# LeftBar2_SchDoc.net
KiCad netlist of a schematic drawn in Altium Designer
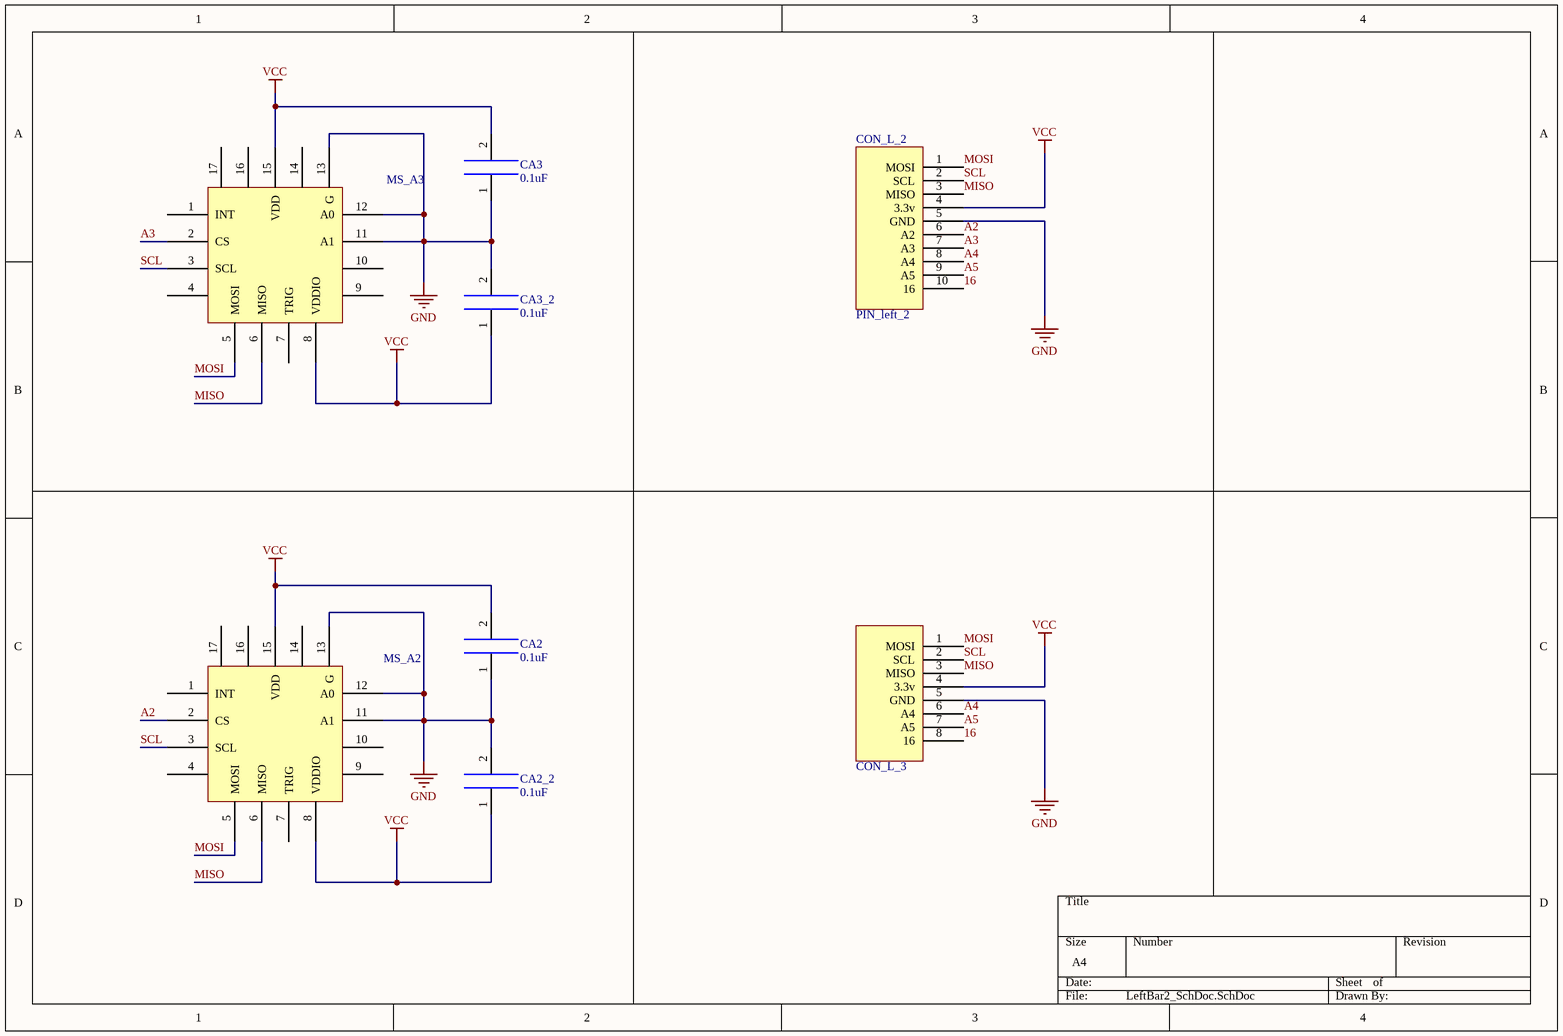
[diagram p0: LeftBar2_SchDoc.SchDoc]

(export (version "E")
  (design (tool "Eeschema 10.0.6"))
  (components
    (comp (ref "CA2")
      (value "0.1uF")
      (footprint "CAP_0603")
      (description "Capacitance")
      (libsource (lib "MagWaySchlib") (part "CAP"))
    )
    (comp (ref "CA2_2")
      (value "0.1uF")
      (footprint "CAP_0603")
      (description "Capacitance")
      (libsource (lib "MagWaySchlib") (part "CAP"))
    )
    (comp (ref "CA3")
      (value "0.1uF")
      (footprint "CAP_0603")
      (description "Capacitance")
      (libsource (lib "MagWaySchlib") (part "CAP"))
    )
    (comp (ref "CA3_2")
      (value "0.1uF")
      (footprint "CAP_0603")
      (description "Capacitance")
      (libsource (lib "MagWaySchlib") (part "CAP"))
    )
    (comp (ref "CON_L_2")
      (value "PIN_left_2")
      (footprint "PIN_Left_2")
      (libsource (lib "MagWaySchlib") (part "PIN_left_2"))
    )
    (comp (ref "CON_L_3")
      (value "PIN_left")
      (footprint "PIN_Left_3")
      (libsource (lib "MagWaySchlib") (part "PIN_left_3"))
    )
    (comp (ref "MS_A2")
      (value "MLX90393SLW ABA 011 RE")
      (footprint "MLX90393")
      (description "MLX90393 Sensor")
      (libsource (lib "MagWaySchlib") (part "MLX90393SLW ABA 011 RE"))
    )
    (comp (ref "MS_A3")
      (value "MLX90393SLW ABA 011 RE")
      (footprint "MLX90393")
      (description "MLX90393 Sensor")
      (libsource (lib "MagWaySchlib") (part "MLX90393SLW ABA 011 RE"))
    )
  )
  (nets
    (net (code "1") (name "/16") (class "Default")
      (node (ref "CON_L_2") (pin "10") (pinfunction "16_10") (pintype "passive"))
      (node (ref "CON_L_3") (pin "8") (pinfunction "16_8") (pintype "passive"))
    )
    (net (code "2") (name "/A2") (class "Default")
      (node (ref "CON_L_2") (pin "6") (pinfunction "A2_6") (pintype "passive"))
      (node (ref "MS_A2") (pin "2") (pinfunction "CS_2") (pintype "passive"))
    )
    (net (code "3") (name "/A3") (class "Default")
      (node (ref "CON_L_2") (pin "7") (pinfunction "A3_7") (pintype "passive"))
      (node (ref "MS_A3") (pin "2") (pinfunction "CS_2") (pintype "passive"))
    )
    (net (code "4") (name "/A4") (class "Default")
      (node (ref "CON_L_2") (pin "8") (pinfunction "A4_8") (pintype "passive"))
      (node (ref "CON_L_3") (pin "6") (pinfunction "A4_6") (pintype "passive"))
    )
    (net (code "5") (name "/A5") (class "Default")
      (node (ref "CON_L_2") (pin "9") (pinfunction "A5_9") (pintype "passive"))
      (node (ref "CON_L_3") (pin "7") (pinfunction "A5_7") (pintype "passive"))
    )
    (net (code "6") (name "/MISO") (class "Default")
      (node (ref "CON_L_2") (pin "3") (pinfunction "MISO_3") (pintype "passive"))
      (node (ref "CON_L_3") (pin "3") (pinfunction "MISO_3") (pintype "passive"))
      (node (ref "MS_A2") (pin "6") (pinfunction "MISO_6") (pintype "passive"))
      (node (ref "MS_A3") (pin "6") (pinfunction "MISO_6") (pintype "passive"))
    )
    (net (code "7") (name "/MOSI") (class "Default")
      (node (ref "CON_L_2") (pin "1") (pinfunction "MOSI_1") (pintype "passive"))
      (node (ref "CON_L_3") (pin "1") (pinfunction "MOSI_1") (pintype "passive"))
      (node (ref "MS_A2") (pin "5") (pinfunction "MOSI_5") (pintype "passive"))
      (node (ref "MS_A3") (pin "5") (pinfunction "MOSI_5") (pintype "passive"))
    )
    (net (code "8") (name "/SCL") (class "Default")
      (node (ref "CON_L_2") (pin "2") (pinfunction "SCL_2") (pintype "passive"))
      (node (ref "CON_L_3") (pin "2") (pinfunction "SCL_2") (pintype "passive"))
      (node (ref "MS_A2") (pin "3") (pinfunction "SCL_3") (pintype "passive"))
      (node (ref "MS_A3") (pin "3") (pinfunction "SCL_3") (pintype "passive"))
    )
    (net (code "9") (name "GND") (class "Default")
      (node (ref "CA2") (pin "1") (pintype "passive"))
      (node (ref "CA2_2") (pin "2") (pintype "passive"))
      (node (ref "CA3") (pin "1") (pintype "passive"))
      (node (ref "CA3_2") (pin "2") (pintype "passive"))
      (node (ref "CON_L_2") (pin "5") (pinfunction "GND_5") (pintype "passive"))
      (node (ref "CON_L_3") (pin "5") (pinfunction "GND_5") (pintype "passive"))
      (node (ref "MS_A2") (pin "11") (pinfunction "A1_11") (pintype "passive"))
      (node (ref "MS_A2") (pin "12") (pinfunction "A0_12") (pintype "passive"))
      (node (ref "MS_A2") (pin "13") (pinfunction "G_13") (pintype "passive"))
      (node (ref "MS_A3") (pin "11") (pinfunction "A1_11") (pintype "passive"))
      (node (ref "MS_A3") (pin "12") (pinfunction "A0_12") (pintype "passive"))
      (node (ref "MS_A3") (pin "13") (pinfunction "G_13") (pintype "passive"))
    )
    (net (code "10") (name "VCC") (class "Default")
      (node (ref "CA2") (pin "2") (pintype "passive"))
      (node (ref "CA2_2") (pin "1") (pintype "passive"))
      (node (ref "CA3") (pin "2") (pintype "passive"))
      (node (ref "CA3_2") (pin "1") (pintype "passive"))
      (node (ref "CON_L_2") (pin "4") (pinfunction "3.3v_4") (pintype "passive"))
      (node (ref "CON_L_3") (pin "4") (pinfunction "3.3v_4") (pintype "passive"))
      (node (ref "MS_A2") (pin "15") (pinfunction "VDD_15") (pintype "passive"))
      (node (ref "MS_A2") (pin "8") (pinfunction "VDDIO_8") (pintype "passive"))
      (node (ref "MS_A3") (pin "15") (pinfunction "VDD_15") (pintype "passive"))
      (node (ref "MS_A3") (pin "8") (pinfunction "VDDIO_8") (pintype "passive"))
    )
    (net (code "11") (name "unconnected-(MS_A2-INT-Pad1)") (class "Default")
      (node (ref "MS_A2") (pin "1") (pinfunction "INT_1") (pintype "passive"))
    )
    (net (code "12") (name "unconnected-(MS_A2-Pad4)") (class "Default")
      (node (ref "MS_A2") (pin "4") (pintype "passive"))
    )
    (net (code "13") (name "unconnected-(MS_A2-Pad9)") (class "Default")
      (node (ref "MS_A2") (pin "9") (pintype "passive"))
    )
    (net (code "14") (name "unconnected-(MS_A2-Pad10)") (class "Default")
      (node (ref "MS_A2") (pin "10") (pintype "passive"))
    )
    (net (code "15") (name "unconnected-(MS_A2-Pad14)") (class "Default")
      (node (ref "MS_A2") (pin "14") (pintype "passive"))
    )
    (net (code "16") (name "unconnected-(MS_A2-Pad16)") (class "Default")
      (node (ref "MS_A2") (pin "16") (pintype "passive"))
    )
    (net (code "17") (name "unconnected-(MS_A2-Pad17)") (class "Default")
      (node (ref "MS_A2") (pin "17") (pintype "passive"))
    )
    (net (code "18") (name "unconnected-(MS_A2-TRIG-Pad7)") (class "Default")
      (node (ref "MS_A2") (pin "7") (pinfunction "TRIG_7") (pintype "passive"))
    )
    (net (code "19") (name "unconnected-(MS_A3-INT-Pad1)") (class "Default")
      (node (ref "MS_A3") (pin "1") (pinfunction "INT_1") (pintype "passive"))
    )
    (net (code "20") (name "unconnected-(MS_A3-Pad4)") (class "Default")
      (node (ref "MS_A3") (pin "4") (pintype "passive"))
    )
    (net (code "21") (name "unconnected-(MS_A3-Pad9)") (class "Default")
      (node (ref "MS_A3") (pin "9") (pintype "passive"))
    )
    (net (code "22") (name "unconnected-(MS_A3-Pad10)") (class "Default")
      (node (ref "MS_A3") (pin "10") (pintype "passive"))
    )
    (net (code "23") (name "unconnected-(MS_A3-Pad14)") (class "Default")
      (node (ref "MS_A3") (pin "14") (pintype "passive"))
    )
    (net (code "24") (name "unconnected-(MS_A3-Pad16)") (class "Default")
      (node (ref "MS_A3") (pin "16") (pintype "passive"))
    )
    (net (code "25") (name "unconnected-(MS_A3-Pad17)") (class "Default")
      (node (ref "MS_A3") (pin "17") (pintype "passive"))
    )
    (net (code "26") (name "unconnected-(MS_A3-TRIG-Pad7)") (class "Default")
      (node (ref "MS_A3") (pin "7") (pinfunction "TRIG_7") (pintype "passive"))
    )
  )
)
